# HeartBoard.net
KiCad netlist of a schematic drawn in EAGLE
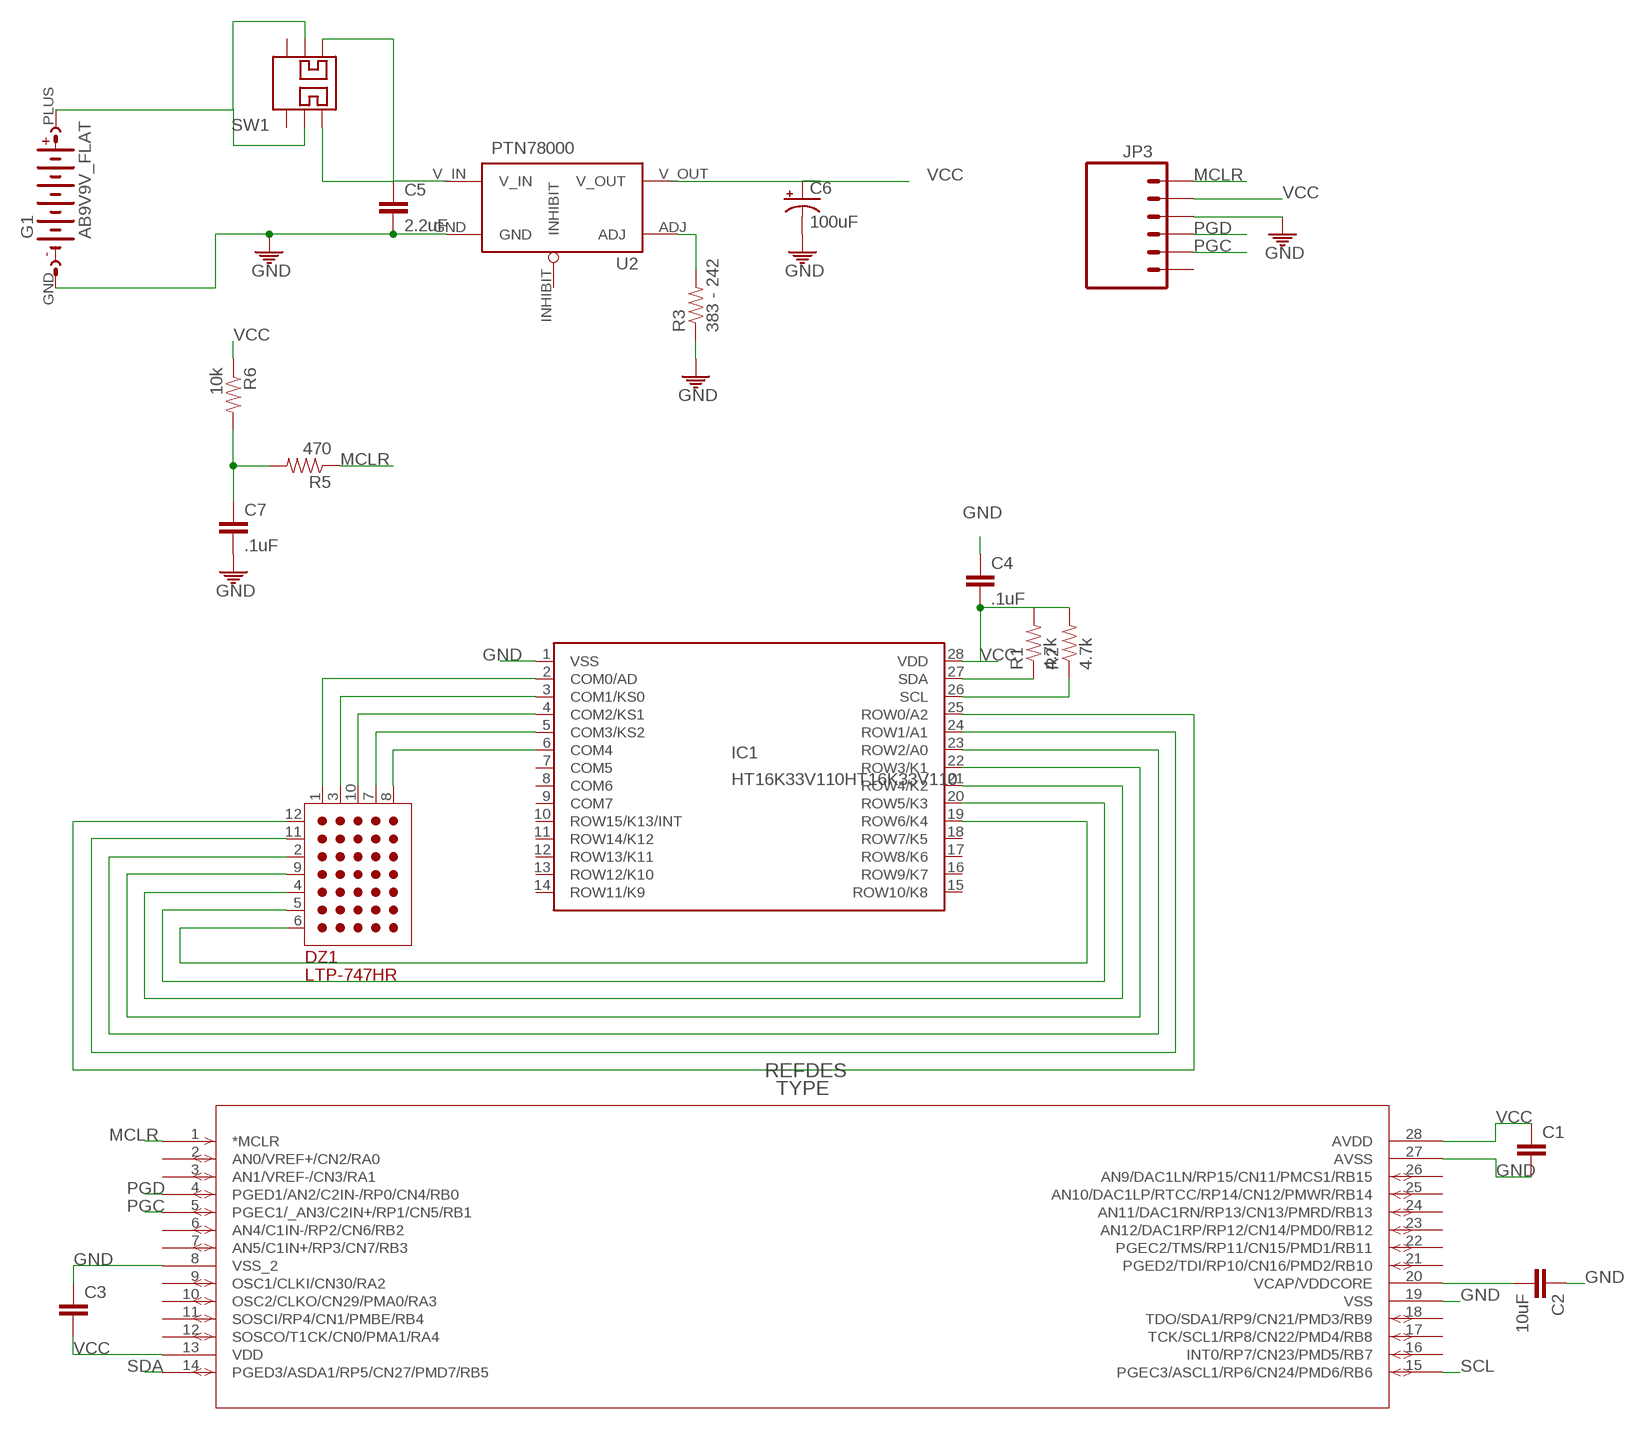
[diagram p0: schematic, sheet 1]

(export (version "E")
  (design (tool "Eeschema 10.0.6"))
  (components
    (comp (ref "C1")
      (value "CAP1206")
      (footprint "eagle-import:1206")
      (libsource (lib "eagle-import") (part "CAP1206"))
    )
    (comp (ref "C2")
      (value "10uF")
      (footprint "eagle-import:1206")
      (libsource (lib "eagle-import") (part "CAP1206"))
    )
    (comp (ref "C3")
      (value "CAP1206")
      (footprint "eagle-import:1206")
      (libsource (lib "eagle-import") (part "CAP1206"))
    )
    (comp (ref "C4")
      (value ".1uF")
      (footprint "eagle-import:1206")
      (libsource (lib "eagle-import") (part "CAP1206"))
    )
    (comp (ref "C5")
      (value "2.2uF")
      (footprint "eagle-import:1206")
      (libsource (lib "eagle-import") (part "CMPE118lib_CAP1206"))
    )
    (comp (ref "C6")
      (value "100uF")
      (footprint "eagle-import:CPOL-RADIAL-100UF-25V")
      (libsource (lib "eagle-import") (part "CAP_POLPTH1"))
    )
    (comp (ref "C7")
      (value ".1uF")
      (footprint "eagle-import:1206")
      (libsource (lib "eagle-import") (part "CMPE118lib_CAP1206"))
    )
    (comp (ref "DZ1")
      (value "LTP-747HR")
      (footprint "eagle-import:LTP-747HR")
      (libsource (lib "eagle-import") (part "LTP-747HR"))
    )
    (comp (ref "G1")
      (value "AB9V9V_FLAT")
      (footprint "eagle-import:BH9VPC")
      (libsource (lib "eagle-import") (part "AB9V9V_FLAT"))
    )
    (comp (ref "IC1")
      (value "HT16K33V110HT16K33V110")
      (footprint "eagle-import:SOP28")
      (libsource (lib "eagle-import") (part "HT16K33V110HT16K33V110"))
    )
    (comp (ref "JP3")
      (value "M06LOCK")
      (footprint "eagle-import:1X06_LOCK")
      (libsource (lib "eagle-import") (part "M06LOCK"))
    )
    (comp (ref "R1")
      (value "4.7k")
      (footprint "eagle-import:0805")
      (libsource (lib "eagle-import") (part "RESISTOR0805-RES"))
    )
    (comp (ref "R2")
      (value "4.7k")
      (footprint "eagle-import:0805")
      (libsource (lib "eagle-import") (part "RESISTOR0805-RES"))
    )
    (comp (ref "R3")
      (value "383 - 242")
      (footprint "eagle-import:0805")
      (libsource (lib "eagle-import") (part "CMPE118lib_RESISTOR0805-RES"))
    )
    (comp (ref "R5")
      (value "470")
      (footprint "eagle-import:0805")
      (libsource (lib "eagle-import") (part "CMPE118lib_RESISTOR0805-RES"))
    )
    (comp (ref "R6")
      (value "10k")
      (footprint "eagle-import:0805")
      (libsource (lib "eagle-import") (part "CMPE118lib_RESISTOR0805-RES"))
    )
    (comp (ref "SW1")
      (value "SLIDE_SWITCH_DPDTTOP")
      (footprint "eagle-import:EG2207")
      (libsource (lib "eagle-import") (part "SLIDE_SWITCH_DPDTTOP"))
    )
    (comp (ref "U$1")
      (value "DSPIC33FJ64GP802")
      (footprint "eagle-import:SOIC28-W_MC")
      (libsource (lib "eagle-import") (part "DSPIC33FJ64GP802"))
    )
    (comp (ref "U2")
      (value "PTN78000")
      (footprint "eagle-import:PTN78000")
      (libsource (lib "eagle-import") (part "PTN78000THROUGH-HOLE"))
    )
  )
  (nets
    (net (code "1") (name "/MCLR") (class "Default")
      (node (ref "JP3") (pin "1") (pinfunction "1_1") (pintype "passive"))
      (node (ref "R5") (pin "1") (pinfunction "1_1") (pintype "passive"))
      (node (ref "U$1") (pin "1") (pinfunction "*MCLR_1") (pintype "passive"))
    )
    (net (code "2") (name "/PGC") (class "Default")
      (node (ref "JP3") (pin "5") (pinfunction "5_5") (pintype "passive"))
      (node (ref "U$1") (pin "5") (pinfunction "PGEC1/_AN3/C2IN+/RP1/CN5/RB1_5") (pintype "passive"))
    )
    (net (code "3") (name "/PGD") (class "Default")
      (node (ref "JP3") (pin "4") (pinfunction "4_4") (pintype "passive"))
      (node (ref "U$1") (pin "4") (pinfunction "PGED1/AN2/C2IN-/RP0/CN4/RB0_4") (pintype "passive"))
    )
    (net (code "4") (name "/SCL") (class "Default")
      (node (ref "IC1") (pin "26") (pinfunction "SCL_26") (pintype "bidirectional"))
      (node (ref "R2") (pin "1") (pinfunction "1_1") (pintype "passive"))
      (node (ref "U$1") (pin "15") (pinfunction "PGEC3/ASCL1/RP6/CN24/PMD6/RB6_15") (pintype "passive"))
    )
    (net (code "5") (name "/SDA") (class "Default")
      (node (ref "IC1") (pin "27") (pinfunction "SDA_27") (pintype "bidirectional"))
      (node (ref "R1") (pin "1") (pinfunction "1_1") (pintype "passive"))
      (node (ref "U$1") (pin "14") (pinfunction "PGED3/ASDA1/RP5/CN27/PMD7/RB5_14") (pintype "passive"))
    )
    (net (code "6") (name "/VCC") (class "Default")
      (node (ref "C1") (pin "1") (pinfunction "1_1") (pintype "passive"))
      (node (ref "C3") (pin "2") (pinfunction "2_2") (pintype "passive"))
      (node (ref "C4") (pin "2") (pinfunction "2_2") (pintype "passive"))
      (node (ref "C6") (pin "1") (pinfunction "+_1") (pintype "passive"))
      (node (ref "IC1") (pin "28") (pinfunction "VDD_28") (pintype "power_in"))
      (node (ref "JP3") (pin "2") (pinfunction "2_2") (pintype "passive"))
      (node (ref "R1") (pin "2") (pinfunction "2_2") (pintype "passive"))
      (node (ref "R2") (pin "2") (pinfunction "2_2") (pintype "passive"))
      (node (ref "R6") (pin "1") (pinfunction "1_1") (pintype "passive"))
      (node (ref "U$1") (pin "13") (pinfunction "VDD_13") (pintype "passive"))
      (node (ref "U$1") (pin "28") (pinfunction "AVDD_28") (pintype "passive"))
      (node (ref "U2") (pin "V_OUT") (pinfunction "V_OUT_V_OUT") (pintype "output"))
    )
    (net (code "7") (name "GND") (class "Default")
      (node (ref "C1") (pin "2") (pinfunction "2_2") (pintype "passive"))
      (node (ref "C2") (pin "1") (pinfunction "1_1") (pintype "passive"))
      (node (ref "C3") (pin "1") (pinfunction "1_1") (pintype "passive"))
      (node (ref "C4") (pin "1") (pinfunction "1_1") (pintype "passive"))
      (node (ref "C5") (pin "2") (pinfunction "2_2") (pintype "passive"))
      (node (ref "C6") (pin "2") (pinfunction "-_2") (pintype "passive"))
      (node (ref "C7") (pin "2") (pinfunction "2_2") (pintype "passive"))
      (node (ref "G1") (pin "GND") (pinfunction "-_GND") (pintype "passive"))
      (node (ref "IC1") (pin "1") (pinfunction "VSS_1") (pintype "power_in"))
      (node (ref "JP3") (pin "3") (pinfunction "3_3") (pintype "passive"))
      (node (ref "R3") (pin "1") (pinfunction "1_1") (pintype "passive"))
      (node (ref "U$1") (pin "19") (pinfunction "VSS_19") (pintype "passive"))
      (node (ref "U$1") (pin "27") (pinfunction "AVSS_27") (pintype "passive"))
      (node (ref "U$1") (pin "8") (pinfunction "VSS_2_8") (pintype "passive"))
      (node (ref "U2") (pin "GND") (pinfunction "GND_GND") (pintype "power_in"))
    )
    (net (code "8") (name "Net-(C5-Pad1)") (class "Default")
      (node (ref "C5") (pin "1") (pinfunction "1_1") (pintype "passive"))
      (node (ref "SW1") (pin "P$1") (pinfunction "P$1_P$1") (pintype "bidirectional"))
      (node (ref "SW1") (pin "P$4") (pinfunction "P$4_P$4") (pintype "bidirectional"))
      (node (ref "U2") (pin "V_IN") (pinfunction "V_IN_V_IN") (pintype "power_in"))
    )
    (net (code "9") (name "Net-(C7-Pad1)") (class "Default")
      (node (ref "C7") (pin "1") (pinfunction "1_1") (pintype "passive"))
      (node (ref "R5") (pin "2") (pinfunction "2_2") (pintype "passive"))
      (node (ref "R6") (pin "2") (pinfunction "2_2") (pintype "passive"))
    )
    (net (code "10") (name "Net-(DZ1-C1)") (class "Default")
      (node (ref "DZ1") (pin "1") (pinfunction "C1_1") (pintype "passive"))
      (node (ref "IC1") (pin "2") (pinfunction "COM0/AD_2") (pintype "bidirectional"))
    )
    (net (code "11") (name "Net-(DZ1-C2)") (class "Default")
      (node (ref "DZ1") (pin "3") (pinfunction "C2_3") (pintype "passive"))
      (node (ref "IC1") (pin "3") (pinfunction "COM1/KS0_3") (pintype "bidirectional"))
    )
    (net (code "12") (name "Net-(DZ1-C3)") (class "Default")
      (node (ref "DZ1") (pin "10") (pinfunction "C3_10") (pintype "passive"))
      (node (ref "IC1") (pin "4") (pinfunction "COM2/KS1_4") (pintype "bidirectional"))
    )
    (net (code "13") (name "Net-(DZ1-C4)") (class "Default")
      (node (ref "DZ1") (pin "7") (pinfunction "C4_7") (pintype "passive"))
      (node (ref "IC1") (pin "5") (pinfunction "COM3/KS2_5") (pintype "bidirectional"))
    )
    (net (code "14") (name "Net-(DZ1-C5)") (class "Default")
      (node (ref "DZ1") (pin "8") (pinfunction "C5_8") (pintype "passive"))
      (node (ref "IC1") (pin "6") (pinfunction "COM4_6") (pintype "bidirectional"))
    )
    (net (code "15") (name "Net-(DZ1-R1)") (class "Default")
      (node (ref "DZ1") (pin "12") (pinfunction "R1_12") (pintype "passive"))
      (node (ref "IC1") (pin "25") (pinfunction "ROW0/A2_25") (pintype "bidirectional"))
    )
    (net (code "16") (name "Net-(DZ1-R2)") (class "Default")
      (node (ref "DZ1") (pin "11") (pinfunction "R2_11") (pintype "passive"))
      (node (ref "IC1") (pin "24") (pinfunction "ROW1/A1_24") (pintype "bidirectional"))
    )
    (net (code "17") (name "Net-(DZ1-R3)") (class "Default")
      (node (ref "DZ1") (pin "2") (pinfunction "R3_2") (pintype "passive"))
      (node (ref "IC1") (pin "23") (pinfunction "ROW2/A0_23") (pintype "bidirectional"))
    )
    (net (code "18") (name "Net-(DZ1-R4)") (class "Default")
      (node (ref "DZ1") (pin "9") (pinfunction "R4_9") (pintype "passive"))
      (node (ref "IC1") (pin "22") (pinfunction "ROW3/K1_22") (pintype "bidirectional"))
    )
    (net (code "19") (name "Net-(DZ1-R5)") (class "Default")
      (node (ref "DZ1") (pin "4") (pinfunction "R5_4") (pintype "passive"))
      (node (ref "IC1") (pin "21") (pinfunction "ROW4/K2_21") (pintype "bidirectional"))
    )
    (net (code "20") (name "Net-(DZ1-R6)") (class "Default")
      (node (ref "DZ1") (pin "5") (pinfunction "R6_5") (pintype "passive"))
      (node (ref "IC1") (pin "20") (pinfunction "ROW5/K3_20") (pintype "bidirectional"))
    )
    (net (code "21") (name "Net-(DZ1-R7)") (class "Default")
      (node (ref "DZ1") (pin "6") (pinfunction "R7_6") (pintype "passive"))
      (node (ref "IC1") (pin "19") (pinfunction "ROW6/K4_19") (pintype "bidirectional"))
    )
    (net (code "22") (name "Net-(G1-+)") (class "Default")
      (node (ref "G1") (pin "PLUS") (pinfunction "+_PLUS") (pintype "passive"))
      (node (ref "SW1") (pin "P$2") (pinfunction "P$2_P$2") (pintype "bidirectional"))
      (node (ref "SW1") (pin "P$5") (pinfunction "P$5_P$5") (pintype "bidirectional"))
    )
    (net (code "23") (name "Net-(R3-Pad2)") (class "Default")
      (node (ref "R3") (pin "2") (pinfunction "2_2") (pintype "passive"))
      (node (ref "U2") (pin "ADJ") (pinfunction "ADJ_ADJ") (pintype "input"))
    )
    (net (code "24") (name "Net-(U$1-VCAP{slash}VDDCORE)") (class "Default")
      (node (ref "C2") (pin "2") (pinfunction "2_2") (pintype "passive"))
      (node (ref "U$1") (pin "20") (pinfunction "VCAP/VDDCORE_20") (pintype "passive"))
    )
    (net (code "25") (name "unconnected-(IC1-COM5-Pad7)") (class "Default")
      (node (ref "IC1") (pin "7") (pinfunction "COM5_7") (pintype "bidirectional"))
    )
    (net (code "26") (name "unconnected-(IC1-COM6-Pad8)") (class "Default")
      (node (ref "IC1") (pin "8") (pinfunction "COM6_8") (pintype "bidirectional"))
    )
    (net (code "27") (name "unconnected-(IC1-COM7-Pad9)") (class "Default")
      (node (ref "IC1") (pin "9") (pinfunction "COM7_9") (pintype "bidirectional"))
    )
    (net (code "28") (name "unconnected-(IC1-ROW7{slash}K5-Pad18)") (class "Default")
      (node (ref "IC1") (pin "18") (pinfunction "ROW7/K5_18") (pintype "bidirectional"))
    )
    (net (code "29") (name "unconnected-(IC1-ROW8{slash}K6-Pad17)") (class "Default")
      (node (ref "IC1") (pin "17") (pinfunction "ROW8/K6_17") (pintype "bidirectional"))
    )
    (net (code "30") (name "unconnected-(IC1-ROW9{slash}K7-Pad16)") (class "Default")
      (node (ref "IC1") (pin "16") (pinfunction "ROW9/K7_16") (pintype "bidirectional"))
    )
    (net (code "31") (name "unconnected-(IC1-ROW10{slash}K8-Pad15)") (class "Default")
      (node (ref "IC1") (pin "15") (pinfunction "ROW10/K8_15") (pintype "bidirectional"))
    )
    (net (code "32") (name "unconnected-(IC1-ROW11{slash}K9-Pad14)") (class "Default")
      (node (ref "IC1") (pin "14") (pinfunction "ROW11/K9_14") (pintype "bidirectional"))
    )
    (net (code "33") (name "unconnected-(IC1-ROW12{slash}K10-Pad13)") (class "Default")
      (node (ref "IC1") (pin "13") (pinfunction "ROW12/K10_13") (pintype "bidirectional"))
    )
    (net (code "34") (name "unconnected-(IC1-ROW13{slash}K11-Pad12)") (class "Default")
      (node (ref "IC1") (pin "12") (pinfunction "ROW13/K11_12") (pintype "bidirectional"))
    )
    (net (code "35") (name "unconnected-(IC1-ROW14{slash}K12-Pad11)") (class "Default")
      (node (ref "IC1") (pin "11") (pinfunction "ROW14/K12_11") (pintype "bidirectional"))
    )
    (net (code "36") (name "unconnected-(IC1-ROW15{slash}K13{slash}INT-Pad10)") (class "Default")
      (node (ref "IC1") (pin "10") (pinfunction "ROW15/K13/INT_10") (pintype "bidirectional"))
    )
    (net (code "37") (name "unconnected-(JP3-Pad6)") (class "Default")
      (node (ref "JP3") (pin "6") (pinfunction "6_6") (pintype "passive"))
    )
    (net (code "38") (name "unconnected-(SW1-PadP$3)") (class "Default")
      (node (ref "SW1") (pin "P$3") (pinfunction "P$3_P$3") (pintype "bidirectional"))
    )
    (net (code "39") (name "unconnected-(SW1-PadP$6)") (class "Default")
      (node (ref "SW1") (pin "P$6") (pinfunction "P$6_P$6") (pintype "bidirectional"))
    )
    (net (code "40") (name "unconnected-(U$1-AN0{slash}VREF+{slash}CN2{slash}RA0-Pad2)") (class "Default")
      (node (ref "U$1") (pin "2") (pinfunction "AN0/VREF+/CN2/RA0_2") (pintype "passive"))
    )
    (net (code "41") (name "unconnected-(U$1-AN1{slash}VREF-{slash}CN3{slash}RA1-Pad3)") (class "Default")
      (node (ref "U$1") (pin "3") (pinfunction "AN1/VREF-/CN3/RA1_3") (pintype "passive"))
    )
    (net (code "42") (name "unconnected-(U$1-AN4{slash}C1IN-{slash}RP2{slash}CN6{slash}RB2-Pad6)") (class "Default")
      (node (ref "U$1") (pin "6") (pinfunction "AN4/C1IN-/RP2/CN6/RB2_6") (pintype "passive"))
    )
    (net (code "43") (name "unconnected-(U$1-AN5{slash}C1IN+{slash}RP3{slash}CN7{slash}RB3-Pad7)") (class "Default")
      (node (ref "U$1") (pin "7") (pinfunction "AN5/C1IN+/RP3/CN7/RB3_7") (pintype "passive"))
    )
    (net (code "44") (name "unconnected-(U$1-AN9{slash}DAC1LN{slash}RP15{slash}CN11{slash}PMCS1{slash}RB15-Pad26)") (class "Default")
      (node (ref "U$1") (pin "26") (pinfunction "AN9/DAC1LN/RP15/CN11/PMCS1/RB15_26") (pintype "passive"))
    )
    (net (code "45") (name "unconnected-(U$1-AN10{slash}DAC1LP{slash}RTCC{slash}RP14{slash}CN12{slash}PMWR{slash}RB14-Pad25)") (class "Default")
      (node (ref "U$1") (pin "25") (pinfunction "AN10/DAC1LP/RTCC/RP14/CN12/PMWR/RB14_25") (pintype "passive"))
    )
    (net (code "46") (name "unconnected-(U$1-AN11{slash}DAC1RN{slash}RP13{slash}CN13{slash}PMRD{slash}RB13-Pad24)") (class "Default")
      (node (ref "U$1") (pin "24") (pinfunction "AN11/DAC1RN/RP13/CN13/PMRD/RB13_24") (pintype "passive"))
    )
    (net (code "47") (name "unconnected-(U$1-AN12{slash}DAC1RP{slash}RP12{slash}CN14{slash}PMD0{slash}RB12-Pad23)") (class "Default")
      (node (ref "U$1") (pin "23") (pinfunction "AN12/DAC1RP/RP12/CN14/PMD0/RB12_23") (pintype "passive"))
    )
    (net (code "48") (name "unconnected-(U$1-INT0{slash}RP7{slash}CN23{slash}PMD5{slash}RB7-Pad16)") (class "Default")
      (node (ref "U$1") (pin "16") (pinfunction "INT0/RP7/CN23/PMD5/RB7_16") (pintype "passive"))
    )
    (net (code "49") (name "unconnected-(U$1-OSC1{slash}CLKI{slash}CN30{slash}RA2-Pad9)") (class "Default")
      (node (ref "U$1") (pin "9") (pinfunction "OSC1/CLKI/CN30/RA2_9") (pintype "passive"))
    )
    (net (code "50") (name "unconnected-(U$1-OSC2{slash}CLKO{slash}CN29{slash}PMA0{slash}RA3-Pad10)") (class "Default")
      (node (ref "U$1") (pin "10") (pinfunction "OSC2/CLKO/CN29/PMA0/RA3_10") (pintype "passive"))
    )
    (net (code "51") (name "unconnected-(U$1-PGEC2{slash}TMS{slash}RP11{slash}CN15{slash}PMD1{slash}RB11-Pad22)") (class "Default")
      (node (ref "U$1") (pin "22") (pinfunction "PGEC2/TMS/RP11/CN15/PMD1/RB11_22") (pintype "passive"))
    )
    (net (code "52") (name "unconnected-(U$1-PGED2{slash}TDI{slash}RP10{slash}CN16{slash}PMD2{slash}RB10-Pad21)") (class "Default")
      (node (ref "U$1") (pin "21") (pinfunction "PGED2/TDI/RP10/CN16/PMD2/RB10_21") (pintype "passive"))
    )
    (net (code "53") (name "unconnected-(U$1-SOSCI{slash}RP4{slash}CN1{slash}PMBE{slash}RB4-Pad11)") (class "Default")
      (node (ref "U$1") (pin "11") (pinfunction "SOSCI/RP4/CN1/PMBE/RB4_11") (pintype "passive"))
    )
    (net (code "54") (name "unconnected-(U$1-SOSCO{slash}T1CK{slash}CN0{slash}PMA1{slash}RA4-Pad12)") (class "Default")
      (node (ref "U$1") (pin "12") (pinfunction "SOSCO/T1CK/CN0/PMA1/RA4_12") (pintype "passive"))
    )
    (net (code "55") (name "unconnected-(U$1-TCK{slash}SCL1{slash}RP8{slash}CN22{slash}PMD4{slash}RB8-Pad17)") (class "Default")
      (node (ref "U$1") (pin "17") (pinfunction "TCK/SCL1/RP8/CN22/PMD4/RB8_17") (pintype "passive"))
    )
    (net (code "56") (name "unconnected-(U$1-TDO{slash}SDA1{slash}RP9{slash}CN21{slash}PMD3{slash}RB9-Pad18)") (class "Default")
      (node (ref "U$1") (pin "18") (pinfunction "TDO/SDA1/RP9/CN21/PMD3/RB9_18") (pintype "passive"))
    )
    (net (code "57") (name "unconnected-(U2-PadINHIBIT)") (class "Default")
      (node (ref "U2") (pin "INHIBIT") (pinfunction "INHIBIT_INHIBIT") (pintype "input"))
    )
  )
)
